# RasPiTimePowerSWv_1_5.net
KiCad netlist of a schematic drawn in EAGLE
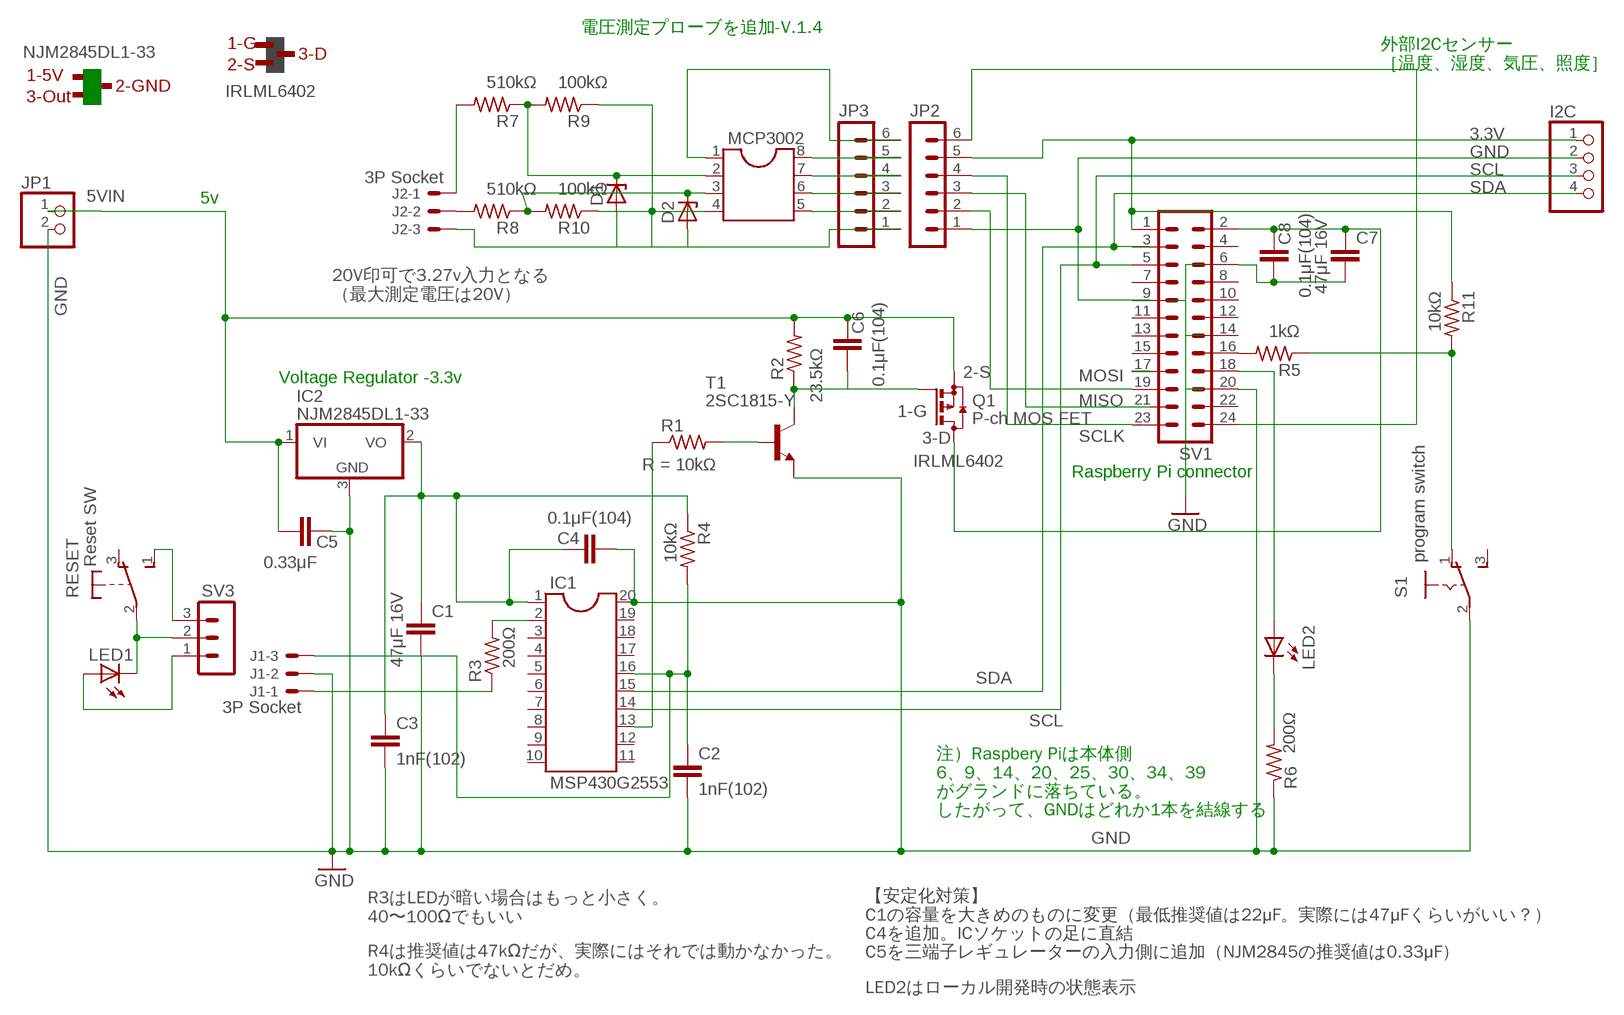
[diagram p0: schematic, sheet 1]

(export (version "E")
  (design (tool "Eeschema 10.0.6"))
  (components
    (comp (ref "C1")
      (value "47μF 16V")
      (footprint "eagle-import:C075-042X103")
      (libsource (lib "eagle-import") (part "C-EU075-042X103"))
    )
    (comp (ref "C2")
      (value "1nF(102)")
      (footprint "eagle-import:C025-024X044")
      (libsource (lib "eagle-import") (part "C-EU025-024X044"))
    )
    (comp (ref "C3")
      (value "1nF(102)")
      (footprint "eagle-import:C025-024X044")
      (libsource (lib "eagle-import") (part "C-EU025-024X044"))
    )
    (comp (ref "C4")
      (value "0.1μF(104)")
      (footprint "eagle-import:C025-024X044")
      (libsource (lib "eagle-import") (part "C-EU025-024X044"))
    )
    (comp (ref "C5")
      (value "0.33μF")
      (footprint "eagle-import:C025-024X044")
      (libsource (lib "eagle-import") (part "C-EU025-024X044"))
    )
    (comp (ref "C6")
      (value "0.1μF(104)")
      (footprint "eagle-import:C025-024X044")
      (libsource (lib "eagle-import") (part "C-EU025-024X044"))
    )
    (comp (ref "C7")
      (value "47μF 16V")
      (footprint "eagle-import:C075-042X103")
      (libsource (lib "eagle-import") (part "C-EU075-042X103"))
    )
    (comp (ref "C8")
      (value "0.1μF(104)")
      (footprint "eagle-import:C025-024X044")
      (libsource (lib "eagle-import") (part "C-EU025-024X044"))
    )
    (comp (ref "D1")
      (value "ZENER-DIODEDO34-7")
      (footprint "eagle-import:DO34Z7")
      (libsource (lib "eagle-import") (part "ZENER-DIODEDO34-7"))
    )
    (comp (ref "D2")
      (value "ZENER-DIODEDO34-7")
      (footprint "eagle-import:DO34Z7")
      (libsource (lib "eagle-import") (part "ZENER-DIODEDO34-7"))
    )
    (comp (ref "I2C")
      (value "PINHD-1X4")
      (footprint "eagle-import:1X04")
      (libsource (lib "eagle-import") (part "PINHD-1X4"))
    )
    (comp (ref "IC1")
      (value "MSP430G2553")
      (footprint "eagle-import:SOCKET-20")
      (libsource (lib "eagle-import") (part "DIL20S"))
    )
    (comp (ref "IC2")
      (value "NJM2845DL1-33")
      (footprint "eagle-import:TO252")
      (libsource (lib "eagle-import") (part "78DT18"))
    )
    (comp (ref "J1")
      (value "3P Socket")
      (footprint "eagle-import:6410-03")
      (libsource (lib "eagle-import") (part "22-?-0327-2031"))
    )
    (comp (ref "J2")
      (value "3P Socket")
      (footprint "eagle-import:6410-03")
      (libsource (lib "eagle-import") (part "22-?-0327-2031"))
    )
    (comp (ref "JP1")
      (value "PINHD-1X2")
      (footprint "eagle-import:1X02")
      (libsource (lib "eagle-import") (part "PINHD-1X2"))
    )
    (comp (ref "JP2")
      (value "MA06-1")
      (footprint "eagle-import:MA06-1")
      (libsource (lib "eagle-import") (part "MA06-1"))
    )
    (comp (ref "JP3")
      (value "MA06-1")
      (footprint "eagle-import:MA06-1")
      (libsource (lib "eagle-import") (part "MA06-1"))
    )
    (comp (ref "LED1")
      (value "TLLG4400")
      (footprint "eagle-import:LED3MM")
      (fields (field (name "MF") "VISHAY SEMICONDUCTOR"))
      (libsource (lib "eagle-import") (part "TLLG4400"))
    )
    (comp (ref "LED2")
      (value "TLLG4400")
      (footprint "eagle-import:LED3MM")
      (fields (field (name "MF") "VISHAY SEMICONDUCTOR"))
      (libsource (lib "eagle-import") (part "TLLG4400"))
    )
    (comp (ref "MCP3002")
      (value "DIL8")
      (footprint "eagle-import:DIL08")
      (libsource (lib "eagle-import") (part "DIL8"))
    )
    (comp (ref "Q1")
      (value "P-ch MOS FET")
      (footprint "eagle-import:SOT23")
      (libsource (lib "eagle-import") (part "BSS84"))
    )
    (comp (ref "R1")
      (value "R-US_MELF0102W")
      (footprint "eagle-import:MINI_MELF-0102W")
      (fields (field (name "R") "10kΩ"))
      (libsource (lib "eagle-import") (part "R-US_MELF0102W"))
    )
    (comp (ref "R2")
      (value "R-US_MELF0102W")
      (footprint "eagle-import:MINI_MELF-0102W")
      (fields (field (name "1K") "23.5kΩ"))
      (libsource (lib "eagle-import") (part "R-US_MELF0102W"))
    )
    (comp (ref "R3")
      (value "R-US_MELF0102W")
      (footprint "eagle-import:MINI_MELF-0102W")
      (fields (field (name "R") "200Ω"))
      (libsource (lib "eagle-import") (part "R-US_MELF0102W"))
    )
    (comp (ref "R4")
      (value "10kΩ")
      (footprint "eagle-import:MINI_MELF-0102W")
      (libsource (lib "eagle-import") (part "R-US_MELF0102W"))
    )
    (comp (ref "R5")
      (value "R-US_MELF0102W")
      (footprint "eagle-import:MINI_MELF-0102W")
      (fields (field (name "1K") "1kΩ"))
      (libsource (lib "eagle-import") (part "R-US_MELF0102W"))
    )
    (comp (ref "R6")
      (value "R-US_MELF0102W")
      (footprint "eagle-import:MINI_MELF-0102W")
      (fields (field (name "R") "200Ω"))
      (libsource (lib "eagle-import") (part "R-US_MELF0102W"))
    )
    (comp (ref "R7")
      (value "R-US_MELF0102W")
      (footprint "eagle-import:MINI_MELF-0102W")
      (fields (field (name "1K") "510kΩ"))
      (libsource (lib "eagle-import") (part "R-US_MELF0102W"))
    )
    (comp (ref "R8")
      (value "R-US_MELF0102W")
      (footprint "eagle-import:MINI_MELF-0102W")
      (fields (field (name "1K") "510kΩ"))
      (libsource (lib "eagle-import") (part "R-US_MELF0102W"))
    )
    (comp (ref "R9")
      (value "R-US_MELF0102W")
      (footprint "eagle-import:MINI_MELF-0102W")
      (fields (field (name "1K") "100kΩ"))
      (libsource (lib "eagle-import") (part "R-US_MELF0102W"))
    )
    (comp (ref "R10")
      (value "R-US_MELF0102W")
      (footprint "eagle-import:MINI_MELF-0102W")
      (fields (field (name "1K") "100kΩ"))
      (libsource (lib "eagle-import") (part "R-US_MELF0102W"))
    )
    (comp (ref "R11")
      (value "10kΩ")
      (footprint "eagle-import:MINI_MELF-0102W")
      (libsource (lib "eagle-import") (part "R-US_MELF0102W"))
    )
    (comp (ref "RESET")
      (value "Reset SW")
      (footprint "eagle-import:9450-1")
      (libsource (lib "eagle-import") (part "9450-1"))
    )
    (comp (ref "S1")
      (value "program switch")
      (footprint "eagle-import:255SB")
      (libsource (lib "eagle-import") (part "255SB"))
    )
    (comp (ref "SV1")
      (value "MA12-2")
      (footprint "eagle-import:MA12-2")
      (libsource (lib "eagle-import") (part "MA12-2"))
    )
    (comp (ref "SV3")
      (value "MA03-1")
      (footprint "eagle-import:MA03-1")
      (libsource (lib "eagle-import") (part "MA03-1"))
    )
    (comp (ref "T1")
      (value "2SC1815-Y")
      (footprint "eagle-import:TO92-ECB")
      (libsource (lib "eagle-import") (part "2SC1815"))
    )
  )
  (nets
    (net (code "1") (name "/3.3V") (class "Default")
      (node (ref "C1") (pin "1") (pinfunction "1_1") (pintype "passive"))
      (node (ref "C3") (pin "1") (pinfunction "1_1") (pintype "passive"))
      (node (ref "C4") (pin "1") (pinfunction "1_1") (pintype "passive"))
      (node (ref "I2C") (pin "1") (pinfunction "1_1") (pintype "passive"))
      (node (ref "IC1") (pin "1") (pinfunction "1_1") (pintype "passive"))
      (node (ref "IC2") (pin "2") (pinfunction "VO_2") (pintype "passive"))
      (node (ref "JP2") (pin "5") (pinfunction "5_5") (pintype "passive"))
      (node (ref "R11") (pin "1") (pinfunction "1_1") (pintype "passive"))
      (node (ref "R4") (pin "1") (pinfunction "1_1") (pintype "passive"))
      (node (ref "SV1") (pin "1") (pinfunction "1_1") (pintype "passive"))
    )
    (net (code "2") (name "/5VIN") (class "Default")
      (node (ref "C5") (pin "2") (pinfunction "2_2") (pintype "passive"))
      (node (ref "C6") (pin "1") (pinfunction "1_1") (pintype "passive"))
      (node (ref "IC2") (pin "1") (pinfunction "VI_1") (pintype "input"))
      (node (ref "JP1") (pin "1") (pinfunction "1_1") (pintype "passive"))
      (node (ref "Q1") (pin "2") (pinfunction "S_2") (pintype "passive"))
      (node (ref "R2") (pin "2") (pinfunction "2_2") (pintype "passive"))
    )
    (net (code "3") (name "/MISO") (class "Default")
      (node (ref "JP2") (pin "3") (pinfunction "3_3") (pintype "passive"))
      (node (ref "SV1") (pin "21") (pinfunction "21_21") (pintype "passive"))
    )
    (net (code "4") (name "/MOSI") (class "Default")
      (node (ref "JP2") (pin "2") (pinfunction "2_2") (pintype "passive"))
      (node (ref "SV1") (pin "19") (pinfunction "19_19") (pintype "passive"))
    )
    (net (code "5") (name "/SCL") (class "Default")
      (node (ref "I2C") (pin "3") (pinfunction "3_3") (pintype "passive"))
      (node (ref "IC1") (pin "14") (pinfunction "14_14") (pintype "passive"))
      (node (ref "SV1") (pin "5") (pinfunction "5_5") (pintype "passive"))
    )
    (net (code "6") (name "/SCLK") (class "Default")
      (node (ref "JP2") (pin "4") (pinfunction "4_4") (pintype "passive"))
      (node (ref "SV1") (pin "23") (pinfunction "23_23") (pintype "passive"))
    )
    (net (code "7") (name "/SDA") (class "Default")
      (node (ref "I2C") (pin "4") (pinfunction "4_4") (pintype "passive"))
      (node (ref "IC1") (pin "15") (pinfunction "15_15") (pintype "passive"))
      (node (ref "SV1") (pin "3") (pinfunction "3_3") (pintype "passive"))
    )
    (net (code "8") (name "GND") (class "Default")
      (node (ref "C1") (pin "2") (pinfunction "2_2") (pintype "passive"))
      (node (ref "C2") (pin "2") (pinfunction "2_2") (pintype "passive"))
      (node (ref "C3") (pin "2") (pinfunction "2_2") (pintype "passive"))
      (node (ref "C4") (pin "2") (pinfunction "2_2") (pintype "passive"))
      (node (ref "C5") (pin "1") (pinfunction "1_1") (pintype "passive"))
      (node (ref "I2C") (pin "2") (pinfunction "2_2") (pintype "passive"))
      (node (ref "IC1") (pin "20") (pinfunction "20_20") (pintype "passive"))
      (node (ref "IC2") (pin "3") (pinfunction "GND_3") (pintype "passive"))
      (node (ref "J1") (pin "2") (pinfunction "S_2") (pintype "passive"))
      (node (ref "JP1") (pin "2") (pinfunction "2_2") (pintype "passive"))
      (node (ref "JP2") (pin "1") (pinfunction "1_1") (pintype "passive"))
      (node (ref "R6") (pin "1") (pinfunction "1_1") (pintype "passive"))
      (node (ref "S1") (pin "2") (pinfunction "P_2") (pintype "passive"))
      (node (ref "SV1") (pin "20") (pinfunction "20_20") (pintype "passive"))
      (node (ref "SV1") (pin "9") (pinfunction "9_9") (pintype "passive"))
      (node (ref "T1") (pin "E") (pinfunction "E_E") (pintype "passive"))
    )
    (net (code "9") (name "Net-(C7-Pad2)") (class "Default")
      (node (ref "C7") (pin "2") (pinfunction "2_2") (pintype "passive"))
      (node (ref "C8") (pin "2") (pinfunction "2_2") (pintype "passive"))
      (node (ref "SV1") (pin "6") (pinfunction "6_6") (pintype "passive"))
    )
    (net (code "10") (name "Net-(D1-PadC)") (class "Default")
      (node (ref "D1") (pin "C") (pinfunction "C_C") (pintype "passive"))
      (node (ref "MCP3002") (pin "2") (pinfunction "2_2") (pintype "passive"))
      (node (ref "R7") (pin "1") (pinfunction "1_1") (pintype "passive"))
      (node (ref "R9") (pin "2") (pinfunction "2_2") (pintype "passive"))
    )
    (net (code "11") (name "Net-(D2-PadC)") (class "Default")
      (node (ref "D2") (pin "C") (pinfunction "C_C") (pintype "passive"))
      (node (ref "MCP3002") (pin "3") (pinfunction "3_3") (pintype "passive"))
      (node (ref "R10") (pin "2") (pinfunction "2_2") (pintype "passive"))
      (node (ref "R8") (pin "1") (pinfunction "1_1") (pintype "passive"))
    )
    (net (code "12") (name "Net-(IC1-Pad2)") (class "Default")
      (node (ref "IC1") (pin "2") (pinfunction "2_2") (pintype "passive"))
      (node (ref "R3") (pin "2") (pinfunction "2_2") (pintype "passive"))
    )
    (net (code "13") (name "Net-(IC1-Pad13)") (class "Default")
      (node (ref "IC1") (pin "13") (pinfunction "13_13") (pintype "passive"))
      (node (ref "R1") (pin "1") (pinfunction "1_1") (pintype "passive"))
    )
    (net (code "14") (name "Net-(J1A-S)") (class "Default")
      (node (ref "J1") (pin "1") (pinfunction "S_1") (pintype "passive"))
      (node (ref "R3") (pin "1") (pinfunction "1_1") (pintype "passive"))
    )
    (net (code "15") (name "Net-(J1C-S)") (class "Default")
      (node (ref "C2") (pin "1") (pinfunction "1_1") (pintype "passive"))
      (node (ref "IC1") (pin "16") (pinfunction "16_16") (pintype "passive"))
      (node (ref "J1") (pin "3") (pinfunction "S_3") (pintype "passive"))
      (node (ref "R4") (pin "2") (pinfunction "2_2") (pintype "passive"))
    )
    (net (code "16") (name "Net-(J2A-S)") (class "Default")
      (node (ref "J2") (pin "1") (pinfunction "S_1") (pintype "passive"))
      (node (ref "R7") (pin "2") (pinfunction "2_2") (pintype "passive"))
    )
    (net (code "17") (name "Net-(J2B-S)") (class "Default")
      (node (ref "J2") (pin "2") (pinfunction "S_2") (pintype "passive"))
      (node (ref "R8") (pin "2") (pinfunction "2_2") (pintype "passive"))
    )
    (net (code "18") (name "Net-(J2C-S)") (class "Default")
      (node (ref "D1") (pin "A") (pinfunction "A_A") (pintype "passive"))
      (node (ref "D2") (pin "A") (pinfunction "A_A") (pintype "passive"))
      (node (ref "J2") (pin "3") (pinfunction "S_3") (pintype "passive"))
      (node (ref "JP3") (pin "1") (pinfunction "1_1") (pintype "passive"))
      (node (ref "MCP3002") (pin "4") (pinfunction "4_4") (pintype "passive"))
      (node (ref "R10") (pin "1") (pinfunction "1_1") (pintype "passive"))
      (node (ref "R9") (pin "1") (pinfunction "1_1") (pintype "passive"))
    )
    (net (code "19") (name "Net-(JP2-Pad6)") (class "Default")
      (node (ref "JP2") (pin "6") (pinfunction "6_6") (pintype "passive"))
      (node (ref "SV1") (pin "24") (pinfunction "24_24") (pintype "passive"))
    )
    (net (code "20") (name "Net-(JP3-Pad2)") (class "Default")
      (node (ref "JP3") (pin "2") (pinfunction "2_2") (pintype "passive"))
      (node (ref "MCP3002") (pin "5") (pinfunction "5_5") (pintype "passive"))
    )
    (net (code "21") (name "Net-(JP3-Pad3)") (class "Default")
      (node (ref "JP3") (pin "3") (pinfunction "3_3") (pintype "passive"))
      (node (ref "MCP3002") (pin "6") (pinfunction "6_6") (pintype "passive"))
    )
    (net (code "22") (name "Net-(JP3-Pad4)") (class "Default")
      (node (ref "JP3") (pin "4") (pinfunction "4_4") (pintype "passive"))
      (node (ref "MCP3002") (pin "7") (pinfunction "7_7") (pintype "passive"))
    )
    (net (code "23") (name "Net-(JP3-Pad5)") (class "Default")
      (node (ref "JP3") (pin "5") (pinfunction "5_5") (pintype "passive"))
      (node (ref "MCP3002") (pin "8") (pinfunction "8_8") (pintype "passive"))
    )
    (net (code "24") (name "Net-(JP3-Pad6)") (class "Default")
      (node (ref "JP3") (pin "6") (pinfunction "6_6") (pintype "passive"))
      (node (ref "MCP3002") (pin "1") (pinfunction "1_1") (pintype "passive"))
    )
    (net (code "25") (name "Net-(LED1-C)") (class "Default")
      (node (ref "LED1") (pin "K") (pinfunction "C_K") (pintype "passive"))
      (node (ref "RESET") (pin "2") (pinfunction "P_2") (pintype "passive"))
      (node (ref "SV3") (pin "2") (pinfunction "2_2") (pintype "passive"))
    )
    (net (code "26") (name "Net-(LED1-PadA)") (class "Default")
      (node (ref "LED1") (pin "A") (pinfunction "A_A") (pintype "passive"))
      (node (ref "SV3") (pin "1") (pinfunction "1_1") (pintype "passive"))
    )
    (net (code "27") (name "Net-(LED2-C)") (class "Default")
      (node (ref "LED2") (pin "K") (pinfunction "C_K") (pintype "passive"))
      (node (ref "R6") (pin "2") (pinfunction "2_2") (pintype "passive"))
    )
    (net (code "28") (name "Net-(LED2-PadA)") (class "Default")
      (node (ref "LED2") (pin "A") (pinfunction "A_A") (pintype "passive"))
      (node (ref "SV1") (pin "18") (pinfunction "18_18") (pintype "passive"))
    )
    (net (code "29") (name "Net-(Q1-D)") (class "Default")
      (node (ref "C7") (pin "1") (pinfunction "1_1") (pintype "passive"))
      (node (ref "C8") (pin "1") (pinfunction "1_1") (pintype "passive"))
      (node (ref "Q1") (pin "3") (pinfunction "D_3") (pintype "passive"))
      (node (ref "SV1") (pin "2") (pinfunction "2_2") (pintype "passive"))
    )
    (net (code "30") (name "Net-(Q1-G)") (class "Default")
      (node (ref "C6") (pin "2") (pinfunction "2_2") (pintype "passive"))
      (node (ref "Q1") (pin "1") (pinfunction "G_1") (pintype "passive"))
      (node (ref "R2") (pin "1") (pinfunction "1_1") (pintype "passive"))
      (node (ref "T1") (pin "C") (pinfunction "C_C") (pintype "passive"))
    )
    (net (code "31") (name "Net-(R1-Pad2)") (class "Default")
      (node (ref "R1") (pin "2") (pinfunction "2_2") (pintype "passive"))
      (node (ref "T1") (pin "B") (pinfunction "B_B") (pintype "passive"))
    )
    (net (code "32") (name "Net-(R5-Pad2)") (class "Default")
      (node (ref "R5") (pin "2") (pinfunction "2_2") (pintype "passive"))
      (node (ref "SV1") (pin "16") (pinfunction "16_16") (pintype "passive"))
    )
    (net (code "33") (name "Net-(RESET-S)") (class "Default")
      (node (ref "RESET") (pin "1") (pinfunction "S_1") (pintype "passive"))
      (node (ref "SV3") (pin "3") (pinfunction "3_3") (pintype "passive"))
    )
    (net (code "34") (name "Net-(S1-O)") (class "Default")
      (node (ref "R11") (pin "2") (pinfunction "2_2") (pintype "passive"))
      (node (ref "R5") (pin "1") (pinfunction "1_1") (pintype "passive"))
      (node (ref "S1") (pin "1") (pinfunction "O_1") (pintype "passive"))
    )
    (net (code "35") (name "unconnected-(IC1-Pad3)") (class "Default")
      (node (ref "IC1") (pin "3") (pinfunction "3_3") (pintype "passive"))
    )
    (net (code "36") (name "unconnected-(IC1-Pad4)") (class "Default")
      (node (ref "IC1") (pin "4") (pinfunction "4_4") (pintype "passive"))
    )
    (net (code "37") (name "unconnected-(IC1-Pad5)") (class "Default")
      (node (ref "IC1") (pin "5") (pinfunction "5_5") (pintype "passive"))
    )
    (net (code "38") (name "unconnected-(IC1-Pad6)") (class "Default")
      (node (ref "IC1") (pin "6") (pinfunction "6_6") (pintype "passive"))
    )
    (net (code "39") (name "unconnected-(IC1-Pad7)") (class "Default")
      (node (ref "IC1") (pin "7") (pinfunction "7_7") (pintype "passive"))
    )
    (net (code "40") (name "unconnected-(IC1-Pad8)") (class "Default")
      (node (ref "IC1") (pin "8") (pinfunction "8_8") (pintype "passive"))
    )
    (net (code "41") (name "unconnected-(IC1-Pad9)") (class "Default")
      (node (ref "IC1") (pin "9") (pinfunction "9_9") (pintype "passive"))
    )
    (net (code "42") (name "unconnected-(IC1-Pad10)") (class "Default")
      (node (ref "IC1") (pin "10") (pinfunction "10_10") (pintype "passive"))
    )
    (net (code "43") (name "unconnected-(IC1-Pad11)") (class "Default")
      (node (ref "IC1") (pin "11") (pinfunction "11_11") (pintype "passive"))
    )
    (net (code "44") (name "unconnected-(IC1-Pad12)") (class "Default")
      (node (ref "IC1") (pin "12") (pinfunction "12_12") (pintype "passive"))
    )
    (net (code "45") (name "unconnected-(IC1-Pad17)") (class "Default")
      (node (ref "IC1") (pin "17") (pinfunction "17_17") (pintype "passive"))
    )
    (net (code "46") (name "unconnected-(IC1-Pad18)") (class "Default")
      (node (ref "IC1") (pin "18") (pinfunction "18_18") (pintype "passive"))
    )
    (net (code "47") (name "unconnected-(IC1-Pad19)") (class "Default")
      (node (ref "IC1") (pin "19") (pinfunction "19_19") (pintype "passive"))
    )
    (net (code "48") (name "unconnected-(RESET-O-Pad3)") (class "Default")
      (node (ref "RESET") (pin "3") (pinfunction "O_3") (pintype "passive"))
    )
    (net (code "49") (name "unconnected-(S1-S-Pad3)") (class "Default")
      (node (ref "S1") (pin "3") (pinfunction "S_3") (pintype "passive"))
    )
    (net (code "50") (name "unconnected-(SV1-Pad4)") (class "Default")
      (node (ref "SV1") (pin "4") (pinfunction "4_4") (pintype "passive"))
    )
    (net (code "51") (name "unconnected-(SV1-Pad7)") (class "Default")
      (node (ref "SV1") (pin "7") (pinfunction "7_7") (pintype "passive"))
    )
    (net (code "52") (name "unconnected-(SV1-Pad8)") (class "Default")
      (node (ref "SV1") (pin "8") (pinfunction "8_8") (pintype "passive"))
    )
    (net (code "53") (name "unconnected-(SV1-Pad10)") (class "Default")
      (node (ref "SV1") (pin "10") (pinfunction "10_10") (pintype "passive"))
    )
    (net (code "54") (name "unconnected-(SV1-Pad11)") (class "Default")
      (node (ref "SV1") (pin "11") (pinfunction "11_11") (pintype "passive"))
    )
    (net (code "55") (name "unconnected-(SV1-Pad12)") (class "Default")
      (node (ref "SV1") (pin "12") (pinfunction "12_12") (pintype "passive"))
    )
    (net (code "56") (name "unconnected-(SV1-Pad13)") (class "Default")
      (node (ref "SV1") (pin "13") (pinfunction "13_13") (pintype "passive"))
    )
    (net (code "57") (name "unconnected-(SV1-Pad14)") (class "Default")
      (node (ref "SV1") (pin "14") (pinfunction "14_14") (pintype "passive"))
    )
    (net (code "58") (name "unconnected-(SV1-Pad15)") (class "Default")
      (node (ref "SV1") (pin "15") (pinfunction "15_15") (pintype "passive"))
    )
    (net (code "59") (name "unconnected-(SV1-Pad17)") (class "Default")
      (node (ref "SV1") (pin "17") (pinfunction "17_17") (pintype "passive"))
    )
    (net (code "60") (name "unconnected-(SV1-Pad22)") (class "Default")
      (node (ref "SV1") (pin "22") (pinfunction "22_22") (pintype "passive"))
    )
  )
)
